# rele.net
KiCad netlist of a schematic drawn in EAGLE
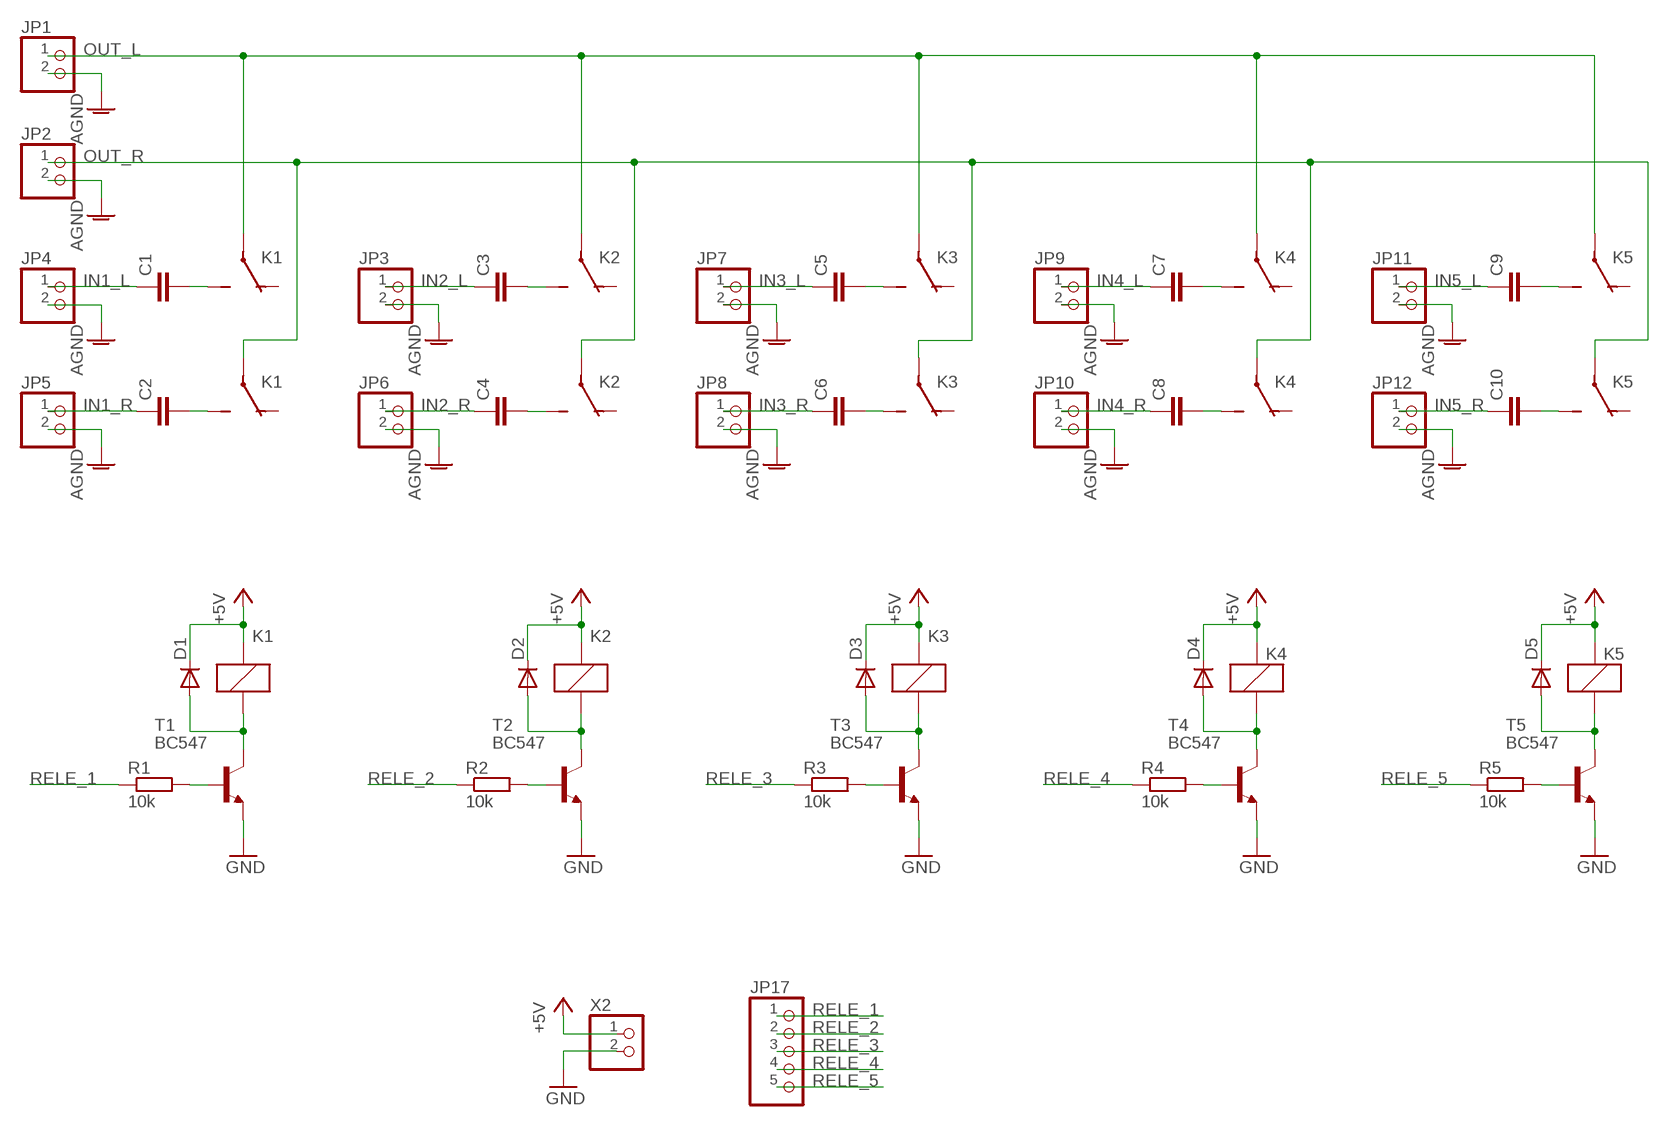
[diagram p0: schematic, sheet 1]

(export (version "E")
  (design (tool "Eeschema 10.0.6"))
  (components
    (comp (ref "C1")
      (value "C-EU050-025X075")
      (footprint "eagle-import:C050-025X075")
      (libsource (lib "eagle-import") (part "C-EU050-025X075"))
    )
    (comp (ref "C2")
      (value "C-EU050-025X075")
      (footprint "eagle-import:C050-025X075")
      (libsource (lib "eagle-import") (part "C-EU050-025X075"))
    )
    (comp (ref "C3")
      (value "C-EU050-025X075")
      (footprint "eagle-import:C050-025X075")
      (libsource (lib "eagle-import") (part "C-EU050-025X075"))
    )
    (comp (ref "C4")
      (value "C-EU050-025X075")
      (footprint "eagle-import:C050-025X075")
      (libsource (lib "eagle-import") (part "C-EU050-025X075"))
    )
    (comp (ref "C5")
      (value "C-EU050-025X075")
      (footprint "eagle-import:C050-025X075")
      (libsource (lib "eagle-import") (part "C-EU050-025X075"))
    )
    (comp (ref "C6")
      (value "C-EU050-025X075")
      (footprint "eagle-import:C050-025X075")
      (libsource (lib "eagle-import") (part "C-EU050-025X075"))
    )
    (comp (ref "C7")
      (value "C-EU050-025X075")
      (footprint "eagle-import:C050-025X075")
      (libsource (lib "eagle-import") (part "C-EU050-025X075"))
    )
    (comp (ref "C8")
      (value "C-EU050-025X075")
      (footprint "eagle-import:C050-025X075")
      (libsource (lib "eagle-import") (part "C-EU050-025X075"))
    )
    (comp (ref "C9")
      (value "C-EU050-025X075")
      (footprint "eagle-import:C050-025X075")
      (libsource (lib "eagle-import") (part "C-EU050-025X075"))
    )
    (comp (ref "C10")
      (value "C-EU050-025X075")
      (footprint "eagle-import:C050-025X075")
      (libsource (lib "eagle-import") (part "C-EU050-025X075"))
    )
    (comp (ref "D1")
      (value "1N4004A")
      (footprint "eagle-import:DO41-5")
      (libsource (lib "eagle-import") (part "1N4004A"))
    )
    (comp (ref "D2")
      (value "1N4004A")
      (footprint "eagle-import:DO41-5")
      (libsource (lib "eagle-import") (part "1N4004A"))
    )
    (comp (ref "D3")
      (value "1N4004A")
      (footprint "eagle-import:DO41-5")
      (libsource (lib "eagle-import") (part "1N4004A"))
    )
    (comp (ref "D4")
      (value "1N4004A")
      (footprint "eagle-import:DO41-5")
      (libsource (lib "eagle-import") (part "1N4004A"))
    )
    (comp (ref "D5")
      (value "1N4004A")
      (footprint "eagle-import:DO41-5")
      (libsource (lib "eagle-import") (part "1N4004A"))
    )
    (comp (ref "JP1")
      (value "PINHD-1X2")
      (footprint "eagle-import:1X02")
      (libsource (lib "eagle-import") (part "PINHD-1X2"))
    )
    (comp (ref "JP2")
      (value "PINHD-1X2")
      (footprint "eagle-import:1X02")
      (libsource (lib "eagle-import") (part "PINHD-1X2"))
    )
    (comp (ref "JP3")
      (value "PINHD-1X2")
      (footprint "eagle-import:1X02")
      (libsource (lib "eagle-import") (part "PINHD-1X2"))
    )
    (comp (ref "JP4")
      (value "PINHD-1X2")
      (footprint "eagle-import:1X02")
      (libsource (lib "eagle-import") (part "PINHD-1X2"))
    )
    (comp (ref "JP5")
      (value "PINHD-1X2")
      (footprint "eagle-import:1X02")
      (libsource (lib "eagle-import") (part "PINHD-1X2"))
    )
    (comp (ref "JP6")
      (value "PINHD-1X2")
      (footprint "eagle-import:1X02")
      (libsource (lib "eagle-import") (part "PINHD-1X2"))
    )
    (comp (ref "JP7")
      (value "PINHD-1X2")
      (footprint "eagle-import:1X02")
      (libsource (lib "eagle-import") (part "PINHD-1X2"))
    )
    (comp (ref "JP8")
      (value "PINHD-1X2")
      (footprint "eagle-import:1X02")
      (libsource (lib "eagle-import") (part "PINHD-1X2"))
    )
    (comp (ref "JP9")
      (value "PINHD-1X2")
      (footprint "eagle-import:1X02")
      (libsource (lib "eagle-import") (part "PINHD-1X2"))
    )
    (comp (ref "JP10")
      (value "PINHD-1X2")
      (footprint "eagle-import:1X02")
      (libsource (lib "eagle-import") (part "PINHD-1X2"))
    )
    (comp (ref "JP11")
      (value "PINHD-1X2")
      (footprint "eagle-import:1X02")
      (libsource (lib "eagle-import") (part "PINHD-1X2"))
    )
    (comp (ref "JP12")
      (value "PINHD-1X2")
      (footprint "eagle-import:1X02")
      (libsource (lib "eagle-import") (part "PINHD-1X2"))
    )
    (comp (ref "JP17")
      (value "PINHD-1X5")
      (footprint "eagle-import:1X05")
      (libsource (lib "eagle-import") (part "PINHD-1X5"))
    )
    (comp (ref "K1")
      (value "MICRO-RELAY")
      (footprint "eagle-import:MICRO-RELAY")
      (libsource (lib "eagle-import") (part "MICRO-RELAY"))
    )
    (comp (ref "K2")
      (value "MICRO-RELAY")
      (footprint "eagle-import:MICRO-RELAY")
      (libsource (lib "eagle-import") (part "MICRO-RELAY"))
    )
    (comp (ref "K3")
      (value "MICRO-RELAY")
      (footprint "eagle-import:MICRO-RELAY")
      (libsource (lib "eagle-import") (part "MICRO-RELAY"))
    )
    (comp (ref "K4")
      (value "MICRO-RELAY")
      (footprint "eagle-import:MICRO-RELAY")
      (libsource (lib "eagle-import") (part "MICRO-RELAY"))
    )
    (comp (ref "K5")
      (value "MICRO-RELAY")
      (footprint "eagle-import:MICRO-RELAY")
      (libsource (lib "eagle-import") (part "MICRO-RELAY"))
    )
    (comp (ref "R1")
      (value "10k")
      (footprint "eagle-import:0207_7")
      (libsource (lib "eagle-import") (part "R-EU_0207/7"))
    )
    (comp (ref "R2")
      (value "10k")
      (footprint "eagle-import:0207_7")
      (libsource (lib "eagle-import") (part "R-EU_0207/7"))
    )
    (comp (ref "R3")
      (value "10k")
      (footprint "eagle-import:0207_7")
      (libsource (lib "eagle-import") (part "R-EU_0207/7"))
    )
    (comp (ref "R4")
      (value "10k")
      (footprint "eagle-import:0207_7")
      (libsource (lib "eagle-import") (part "R-EU_0207/7"))
    )
    (comp (ref "R5")
      (value "10k")
      (footprint "eagle-import:0207_7")
      (libsource (lib "eagle-import") (part "R-EU_0207/7"))
    )
    (comp (ref "T1")
      (value "BC547")
      (footprint "eagle-import:TO92-")
      (libsource (lib "eagle-import") (part "BC547-"))
    )
    (comp (ref "T2")
      (value "BC547")
      (footprint "eagle-import:TO92-")
      (libsource (lib "eagle-import") (part "BC547-"))
    )
    (comp (ref "T3")
      (value "BC547")
      (footprint "eagle-import:TO92-")
      (libsource (lib "eagle-import") (part "BC547-"))
    )
    (comp (ref "T4")
      (value "BC547")
      (footprint "eagle-import:TO92-")
      (libsource (lib "eagle-import") (part "BC547-"))
    )
    (comp (ref "T5")
      (value "BC547")
      (footprint "eagle-import:TO92-")
      (libsource (lib "eagle-import") (part "BC547-"))
    )
    (comp (ref "X2")
      (value "22-23-2021")
      (footprint "eagle-import:22-23-2021")
      (libsource (lib "eagle-import") (part "22-23-2021"))
    )
  )
  (nets
    (net (code "1") (name "+5V") (class "Default")
      (node (ref "D1") (pin "C") (pinfunction "C_C") (pintype "passive"))
      (node (ref "D2") (pin "C") (pinfunction "C_C") (pintype "passive"))
      (node (ref "D3") (pin "C") (pinfunction "C_C") (pintype "passive"))
      (node (ref "D4") (pin "C") (pinfunction "C_C") (pintype "passive"))
      (node (ref "D5") (pin "C") (pinfunction "C_C") (pintype "passive"))
      (node (ref "K1") (pin "A1") (pinfunction "1_A1") (pintype "passive"))
      (node (ref "K2") (pin "A1") (pinfunction "1_A1") (pintype "passive"))
      (node (ref "K3") (pin "A1") (pinfunction "1_A1") (pintype "passive"))
      (node (ref "K4") (pin "A1") (pinfunction "1_A1") (pintype "passive"))
      (node (ref "K5") (pin "A1") (pinfunction "1_A1") (pintype "passive"))
      (node (ref "X2") (pin "1") (pinfunction "1_1") (pintype "passive"))
    )
    (net (code "2") (name "/IN1_L") (class "Default")
      (node (ref "C1") (pin "1") (pinfunction "1_1") (pintype "passive"))
      (node (ref "JP4") (pin "1") (pinfunction "1_1") (pintype "passive"))
    )
    (net (code "3") (name "/IN1_R") (class "Default")
      (node (ref "C2") (pin "1") (pinfunction "1_1") (pintype "passive"))
      (node (ref "JP5") (pin "1") (pinfunction "1_1") (pintype "passive"))
    )
    (net (code "4") (name "/IN2_L") (class "Default")
      (node (ref "C3") (pin "1") (pinfunction "1_1") (pintype "passive"))
      (node (ref "JP3") (pin "1") (pinfunction "1_1") (pintype "passive"))
    )
    (net (code "5") (name "/IN2_R") (class "Default")
      (node (ref "C4") (pin "1") (pinfunction "1_1") (pintype "passive"))
      (node (ref "JP6") (pin "1") (pinfunction "1_1") (pintype "passive"))
    )
    (net (code "6") (name "/IN3_L") (class "Default")
      (node (ref "C5") (pin "1") (pinfunction "1_1") (pintype "passive"))
      (node (ref "JP7") (pin "1") (pinfunction "1_1") (pintype "passive"))
    )
    (net (code "7") (name "/IN3_R") (class "Default")
      (node (ref "C6") (pin "1") (pinfunction "1_1") (pintype "passive"))
      (node (ref "JP8") (pin "1") (pinfunction "1_1") (pintype "passive"))
    )
    (net (code "8") (name "/IN4_L") (class "Default")
      (node (ref "C7") (pin "1") (pinfunction "1_1") (pintype "passive"))
      (node (ref "JP9") (pin "1") (pinfunction "1_1") (pintype "passive"))
    )
    (net (code "9") (name "/IN4_R") (class "Default")
      (node (ref "C8") (pin "1") (pinfunction "1_1") (pintype "passive"))
      (node (ref "JP10") (pin "1") (pinfunction "1_1") (pintype "passive"))
    )
    (net (code "10") (name "/IN5_L") (class "Default")
      (node (ref "C9") (pin "1") (pinfunction "1_1") (pintype "passive"))
      (node (ref "JP11") (pin "1") (pinfunction "1_1") (pintype "passive"))
    )
    (net (code "11") (name "/IN5_R") (class "Default")
      (node (ref "C10") (pin "1") (pinfunction "1_1") (pintype "passive"))
      (node (ref "JP12") (pin "1") (pinfunction "1_1") (pintype "passive"))
    )
    (net (code "12") (name "/OUT_L") (class "Default")
      (node (ref "JP1") (pin "1") (pinfunction "1_1") (pintype "passive"))
      (node (ref "K1") (pin "11") (pinfunction "P_11") (pintype "passive"))
      (node (ref "K2") (pin "11") (pinfunction "P_11") (pintype "passive"))
      (node (ref "K3") (pin "11") (pinfunction "P_11") (pintype "passive"))
      (node (ref "K4") (pin "11") (pinfunction "P_11") (pintype "passive"))
      (node (ref "K5") (pin "11") (pinfunction "P_11") (pintype "passive"))
    )
    (net (code "13") (name "/OUT_R") (class "Default")
      (node (ref "JP2") (pin "1") (pinfunction "1_1") (pintype "passive"))
      (node (ref "K1") (pin "21") (pinfunction "P_21") (pintype "passive"))
      (node (ref "K2") (pin "21") (pinfunction "P_21") (pintype "passive"))
      (node (ref "K3") (pin "21") (pinfunction "P_21") (pintype "passive"))
      (node (ref "K4") (pin "21") (pinfunction "P_21") (pintype "passive"))
      (node (ref "K5") (pin "21") (pinfunction "P_21") (pintype "passive"))
    )
    (net (code "14") (name "/RELE_1") (class "Default")
      (node (ref "JP17") (pin "1") (pinfunction "1_1") (pintype "passive"))
      (node (ref "R1") (pin "1") (pinfunction "1_1") (pintype "passive"))
    )
    (net (code "15") (name "/RELE_2") (class "Default")
      (node (ref "JP17") (pin "2") (pinfunction "2_2") (pintype "passive"))
      (node (ref "R2") (pin "1") (pinfunction "1_1") (pintype "passive"))
    )
    (net (code "16") (name "/RELE_3") (class "Default")
      (node (ref "JP17") (pin "3") (pinfunction "3_3") (pintype "passive"))
      (node (ref "R3") (pin "1") (pinfunction "1_1") (pintype "passive"))
    )
    (net (code "17") (name "/RELE_4") (class "Default")
      (node (ref "JP17") (pin "4") (pinfunction "4_4") (pintype "passive"))
      (node (ref "R4") (pin "1") (pinfunction "1_1") (pintype "passive"))
    )
    (net (code "18") (name "/RELE_5") (class "Default")
      (node (ref "JP17") (pin "5") (pinfunction "5_5") (pintype "passive"))
      (node (ref "R5") (pin "1") (pinfunction "1_1") (pintype "passive"))
    )
    (net (code "19") (name "AGND") (class "Default")
      (node (ref "JP1") (pin "2") (pinfunction "2_2") (pintype "passive"))
      (node (ref "JP10") (pin "2") (pinfunction "2_2") (pintype "passive"))
      (node (ref "JP11") (pin "2") (pinfunction "2_2") (pintype "passive"))
      (node (ref "JP12") (pin "2") (pinfunction "2_2") (pintype "passive"))
      (node (ref "JP2") (pin "2") (pinfunction "2_2") (pintype "passive"))
      (node (ref "JP3") (pin "2") (pinfunction "2_2") (pintype "passive"))
      (node (ref "JP4") (pin "2") (pinfunction "2_2") (pintype "passive"))
      (node (ref "JP5") (pin "2") (pinfunction "2_2") (pintype "passive"))
      (node (ref "JP6") (pin "2") (pinfunction "2_2") (pintype "passive"))
      (node (ref "JP7") (pin "2") (pinfunction "2_2") (pintype "passive"))
      (node (ref "JP8") (pin "2") (pinfunction "2_2") (pintype "passive"))
      (node (ref "JP9") (pin "2") (pinfunction "2_2") (pintype "passive"))
    )
    (net (code "20") (name "GND") (class "Default")
      (node (ref "T1") (pin "1") (pinfunction "E_1") (pintype "passive"))
      (node (ref "T2") (pin "1") (pinfunction "E_1") (pintype "passive"))
      (node (ref "T3") (pin "1") (pinfunction "E_1") (pintype "passive"))
      (node (ref "T4") (pin "1") (pinfunction "E_1") (pintype "passive"))
      (node (ref "T5") (pin "1") (pinfunction "E_1") (pintype "passive"))
      (node (ref "X2") (pin "2") (pinfunction "2_2") (pintype "passive"))
    )
    (net (code "21") (name "Net-(K1A-S)") (class "Default")
      (node (ref "C1") (pin "2") (pinfunction "2_2") (pintype "passive"))
      (node (ref "K1") (pin "14") (pinfunction "S_14") (pintype "passive"))
    )
    (net (code "22") (name "Net-(K1B-S)") (class "Default")
      (node (ref "C2") (pin "2") (pinfunction "2_2") (pintype "passive"))
      (node (ref "K1") (pin "24") (pinfunction "S_24") (pintype "passive"))
    )
    (net (code "23") (name "Net-(K1C-2)") (class "Default")
      (node (ref "D1") (pin "A") (pinfunction "A_A") (pintype "passive"))
      (node (ref "K1") (pin "A2") (pinfunction "2_A2") (pintype "passive"))
      (node (ref "T1") (pin "2") (pinfunction "C_2") (pintype "passive"))
    )
    (net (code "24") (name "Net-(K2A-S)") (class "Default")
      (node (ref "C3") (pin "2") (pinfunction "2_2") (pintype "passive"))
      (node (ref "K2") (pin "14") (pinfunction "S_14") (pintype "passive"))
    )
    (net (code "25") (name "Net-(K2B-S)") (class "Default")
      (node (ref "C4") (pin "2") (pinfunction "2_2") (pintype "passive"))
      (node (ref "K2") (pin "24") (pinfunction "S_24") (pintype "passive"))
    )
    (net (code "26") (name "Net-(K2C-2)") (class "Default")
      (node (ref "D2") (pin "A") (pinfunction "A_A") (pintype "passive"))
      (node (ref "K2") (pin "A2") (pinfunction "2_A2") (pintype "passive"))
      (node (ref "T2") (pin "2") (pinfunction "C_2") (pintype "passive"))
    )
    (net (code "27") (name "Net-(K3A-S)") (class "Default")
      (node (ref "C5") (pin "2") (pinfunction "2_2") (pintype "passive"))
      (node (ref "K3") (pin "14") (pinfunction "S_14") (pintype "passive"))
    )
    (net (code "28") (name "Net-(K3B-S)") (class "Default")
      (node (ref "C6") (pin "2") (pinfunction "2_2") (pintype "passive"))
      (node (ref "K3") (pin "24") (pinfunction "S_24") (pintype "passive"))
    )
    (net (code "29") (name "Net-(K3C-2)") (class "Default")
      (node (ref "D3") (pin "A") (pinfunction "A_A") (pintype "passive"))
      (node (ref "K3") (pin "A2") (pinfunction "2_A2") (pintype "passive"))
      (node (ref "T3") (pin "2") (pinfunction "C_2") (pintype "passive"))
    )
    (net (code "30") (name "Net-(K4A-S)") (class "Default")
      (node (ref "C7") (pin "2") (pinfunction "2_2") (pintype "passive"))
      (node (ref "K4") (pin "14") (pinfunction "S_14") (pintype "passive"))
    )
    (net (code "31") (name "Net-(K4B-S)") (class "Default")
      (node (ref "C8") (pin "2") (pinfunction "2_2") (pintype "passive"))
      (node (ref "K4") (pin "24") (pinfunction "S_24") (pintype "passive"))
    )
    (net (code "32") (name "Net-(K4C-2)") (class "Default")
      (node (ref "D4") (pin "A") (pinfunction "A_A") (pintype "passive"))
      (node (ref "K4") (pin "A2") (pinfunction "2_A2") (pintype "passive"))
      (node (ref "T4") (pin "2") (pinfunction "C_2") (pintype "passive"))
    )
    (net (code "33") (name "Net-(K5A-S)") (class "Default")
      (node (ref "C9") (pin "2") (pinfunction "2_2") (pintype "passive"))
      (node (ref "K5") (pin "14") (pinfunction "S_14") (pintype "passive"))
    )
    (net (code "34") (name "Net-(K5B-S)") (class "Default")
      (node (ref "C10") (pin "2") (pinfunction "2_2") (pintype "passive"))
      (node (ref "K5") (pin "24") (pinfunction "S_24") (pintype "passive"))
    )
    (net (code "35") (name "Net-(K5C-2)") (class "Default")
      (node (ref "D5") (pin "A") (pinfunction "A_A") (pintype "passive"))
      (node (ref "K5") (pin "A2") (pinfunction "2_A2") (pintype "passive"))
      (node (ref "T5") (pin "2") (pinfunction "C_2") (pintype "passive"))
    )
    (net (code "36") (name "Net-(T1-B)") (class "Default")
      (node (ref "R1") (pin "2") (pinfunction "2_2") (pintype "passive"))
      (node (ref "T1") (pin "3") (pinfunction "B_3") (pintype "passive"))
    )
    (net (code "37") (name "Net-(T2-B)") (class "Default")
      (node (ref "R2") (pin "2") (pinfunction "2_2") (pintype "passive"))
      (node (ref "T2") (pin "3") (pinfunction "B_3") (pintype "passive"))
    )
    (net (code "38") (name "Net-(T3-B)") (class "Default")
      (node (ref "R3") (pin "2") (pinfunction "2_2") (pintype "passive"))
      (node (ref "T3") (pin "3") (pinfunction "B_3") (pintype "passive"))
    )
    (net (code "39") (name "Net-(T4-B)") (class "Default")
      (node (ref "R4") (pin "2") (pinfunction "2_2") (pintype "passive"))
      (node (ref "T4") (pin "3") (pinfunction "B_3") (pintype "passive"))
    )
    (net (code "40") (name "Net-(T5-B)") (class "Default")
      (node (ref "R5") (pin "2") (pinfunction "2_2") (pintype "passive"))
      (node (ref "T5") (pin "3") (pinfunction "B_3") (pintype "passive"))
    )
    (net (code "41") (name "unconnected-(K1A-O-Pad12)") (class "Default")
      (node (ref "K1") (pin "12") (pinfunction "O_12") (pintype "passive"))
    )
    (net (code "42") (name "unconnected-(K1B-O-Pad22)") (class "Default")
      (node (ref "K1") (pin "22") (pinfunction "O_22") (pintype "passive"))
    )
    (net (code "43") (name "unconnected-(K2A-O-Pad12)") (class "Default")
      (node (ref "K2") (pin "12") (pinfunction "O_12") (pintype "passive"))
    )
    (net (code "44") (name "unconnected-(K2B-O-Pad22)") (class "Default")
      (node (ref "K2") (pin "22") (pinfunction "O_22") (pintype "passive"))
    )
    (net (code "45") (name "unconnected-(K3A-O-Pad12)") (class "Default")
      (node (ref "K3") (pin "12") (pinfunction "O_12") (pintype "passive"))
    )
    (net (code "46") (name "unconnected-(K3B-O-Pad22)") (class "Default")
      (node (ref "K3") (pin "22") (pinfunction "O_22") (pintype "passive"))
    )
    (net (code "47") (name "unconnected-(K4A-O-Pad12)") (class "Default")
      (node (ref "K4") (pin "12") (pinfunction "O_12") (pintype "passive"))
    )
    (net (code "48") (name "unconnected-(K4B-O-Pad22)") (class "Default")
      (node (ref "K4") (pin "22") (pinfunction "O_22") (pintype "passive"))
    )
    (net (code "49") (name "unconnected-(K5A-O-Pad12)") (class "Default")
      (node (ref "K5") (pin "12") (pinfunction "O_12") (pintype "passive"))
    )
    (net (code "50") (name "unconnected-(K5B-O-Pad22)") (class "Default")
      (node (ref "K5") (pin "22") (pinfunction "O_22") (pintype "passive"))
    )
  )
)
